# x-IMU3-SA-D3.net
KiCad netlist of a schematic drawn in Altium Designer
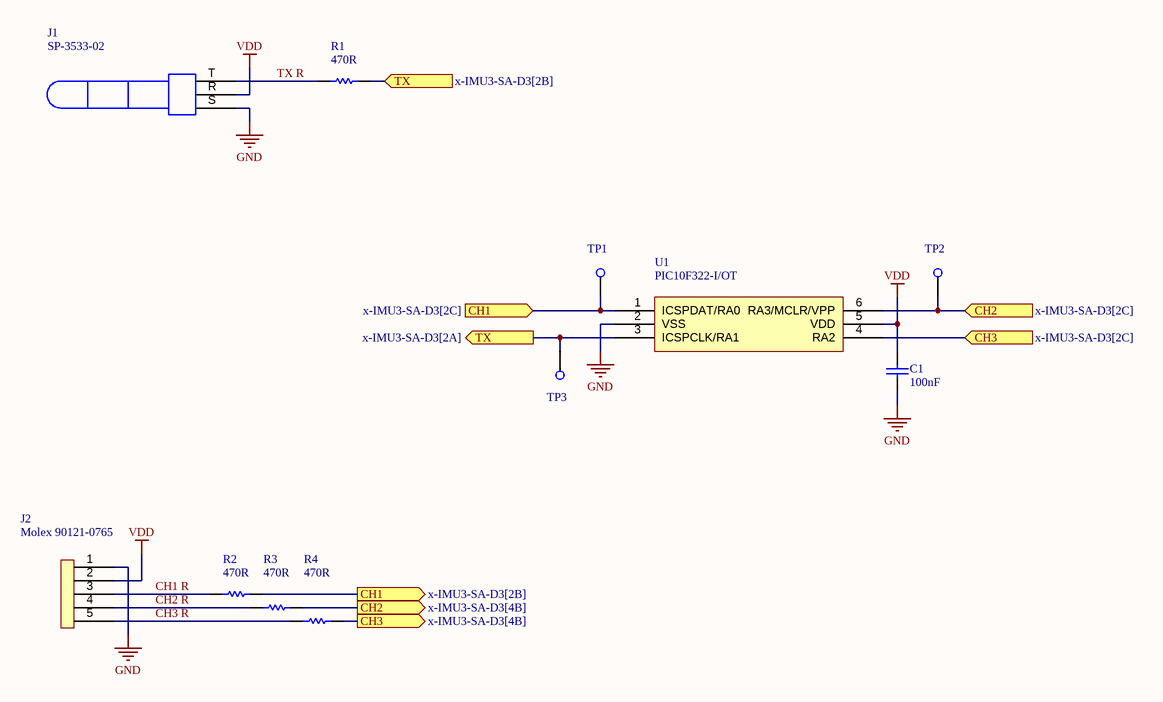
[diagram p0: x-IMU3-SA-D3.SchDoc]

(export (version "E")
  (design (tool "Eeschema 10.0.6"))
  (components
    (comp (ref "C1") (value "100nF") (footprint "Capacitor 0402") (libsource (lib "x-io") (part "Capacitor")))
    (comp (ref "J1")
      (value "SP-3533-02")
      (footprint "SP-3533-02")
      (libsource (lib "x-io") (part "SP-3533-02"))
    )
    (comp (ref "J2")
      (value "Molex 90121-0765")
      (footprint "Molex 90121-0765")
      (libsource (lib "x-io") (part "Molex 90121-0765"))
    )
    (comp (ref "R1") (value "470R") (footprint "Resistor 0402") (libsource (lib "x-io") (part "Resistor")))
    (comp (ref "R2") (value "470R") (footprint "Resistor 0402") (libsource (lib "x-io") (part "Resistor")))
    (comp (ref "R3") (value "470R") (footprint "Resistor 0402") (libsource (lib "x-io") (part "Resistor")))
    (comp (ref "R4") (value "470R") (footprint "Resistor 0402") (libsource (lib "x-io") (part "Resistor")))
    (comp (ref "TP1")
      (value "Test Point")
      (footprint "Test Point 1mm")
      (libsource (lib "x-io") (part "Test Point"))
    )
    (comp (ref "TP2")
      (value "Test Point")
      (footprint "Test Point 1mm")
      (libsource (lib "x-io") (part "Test Point"))
    )
    (comp (ref "TP3")
      (value "Test Point")
      (footprint "Test Point 1mm")
      (libsource (lib "x-io") (part "Test Point"))
    )
    (comp (ref "U1")
      (value "PIC10F322-I/OT")
      (footprint "SOT-23-6")
      (libsource (lib "x-io") (part "PIC10F322-I/OT"))
    )
  )
  (nets
    (net (code "1") (name "/CH1") (class "Default")
      (node (ref "R2") (pin "2") (pinfunction "2_2") (pintype "passive"))
      (node (ref "TP1") (pin "1") (pinfunction "1_1") (pintype "passive"))
      (node (ref "U1") (pin "1") (pinfunction "ICSPDAT/RA0_1") (pintype "passive"))
    )
    (net (code "2") (name "/CH1 R") (class "Default")
      (node (ref "J2") (pin "3") (pinfunction "3_3") (pintype "passive"))
      (node (ref "R2") (pin "1") (pinfunction "1_1") (pintype "passive"))
    )
    (net (code "3") (name "/CH2") (class "Default")
      (node (ref "R3") (pin "2") (pinfunction "2_2") (pintype "passive"))
      (node (ref "TP2") (pin "1") (pinfunction "1_1") (pintype "passive"))
      (node (ref "U1") (pin "6") (pinfunction "RA3/MCLR/VPP_6") (pintype "passive"))
    )
    (net (code "4") (name "/CH2 R") (class "Default")
      (node (ref "J2") (pin "4") (pinfunction "4_4") (pintype "passive"))
      (node (ref "R3") (pin "1") (pinfunction "1_1") (pintype "passive"))
    )
    (net (code "5") (name "/CH3") (class "Default")
      (node (ref "R4") (pin "2") (pinfunction "2_2") (pintype "passive"))
      (node (ref "U1") (pin "4") (pinfunction "RA2_4") (pintype "passive"))
    )
    (net (code "6") (name "/CH3 R") (class "Default")
      (node (ref "J2") (pin "5") (pinfunction "5_5") (pintype "passive"))
      (node (ref "R4") (pin "1") (pinfunction "1_1") (pintype "passive"))
    )
    (net (code "7") (name "/TX") (class "Default")
      (node (ref "R1") (pin "2") (pinfunction "2_2") (pintype "passive"))
      (node (ref "TP3") (pin "1") (pinfunction "1_1") (pintype "passive"))
      (node (ref "U1") (pin "3") (pinfunction "ICSPCLK/RA1_3") (pintype "passive"))
    )
    (net (code "8") (name "/TX R") (class "Default")
      (node (ref "J1") (pin "T") (pinfunction "T_T") (pintype "passive"))
      (node (ref "R1") (pin "1") (pinfunction "1_1") (pintype "passive"))
    )
    (net (code "9") (name "GND") (class "Default")
      (node (ref "C1") (pin "1") (pinfunction "1_1") (pintype "passive"))
      (node (ref "J1") (pin "S") (pinfunction "S_S") (pintype "passive"))
      (node (ref "J2") (pin "1") (pinfunction "1_1") (pintype "passive"))
      (node (ref "U1") (pin "2") (pinfunction "VSS_2") (pintype "passive"))
    )
    (net (code "10") (name "VDD") (class "Default")
      (node (ref "C1") (pin "2") (pinfunction "2_2") (pintype "passive"))
      (node (ref "J1") (pin "R") (pinfunction "R_R") (pintype "passive"))
      (node (ref "J2") (pin "2") (pinfunction "2_2") (pintype "passive"))
      (node (ref "U1") (pin "5") (pinfunction "VDD_5") (pintype "passive"))
    )
  )
)
